# SwitchConnectors.net
KiCad netlist of a schematic drawn in Altium Designer
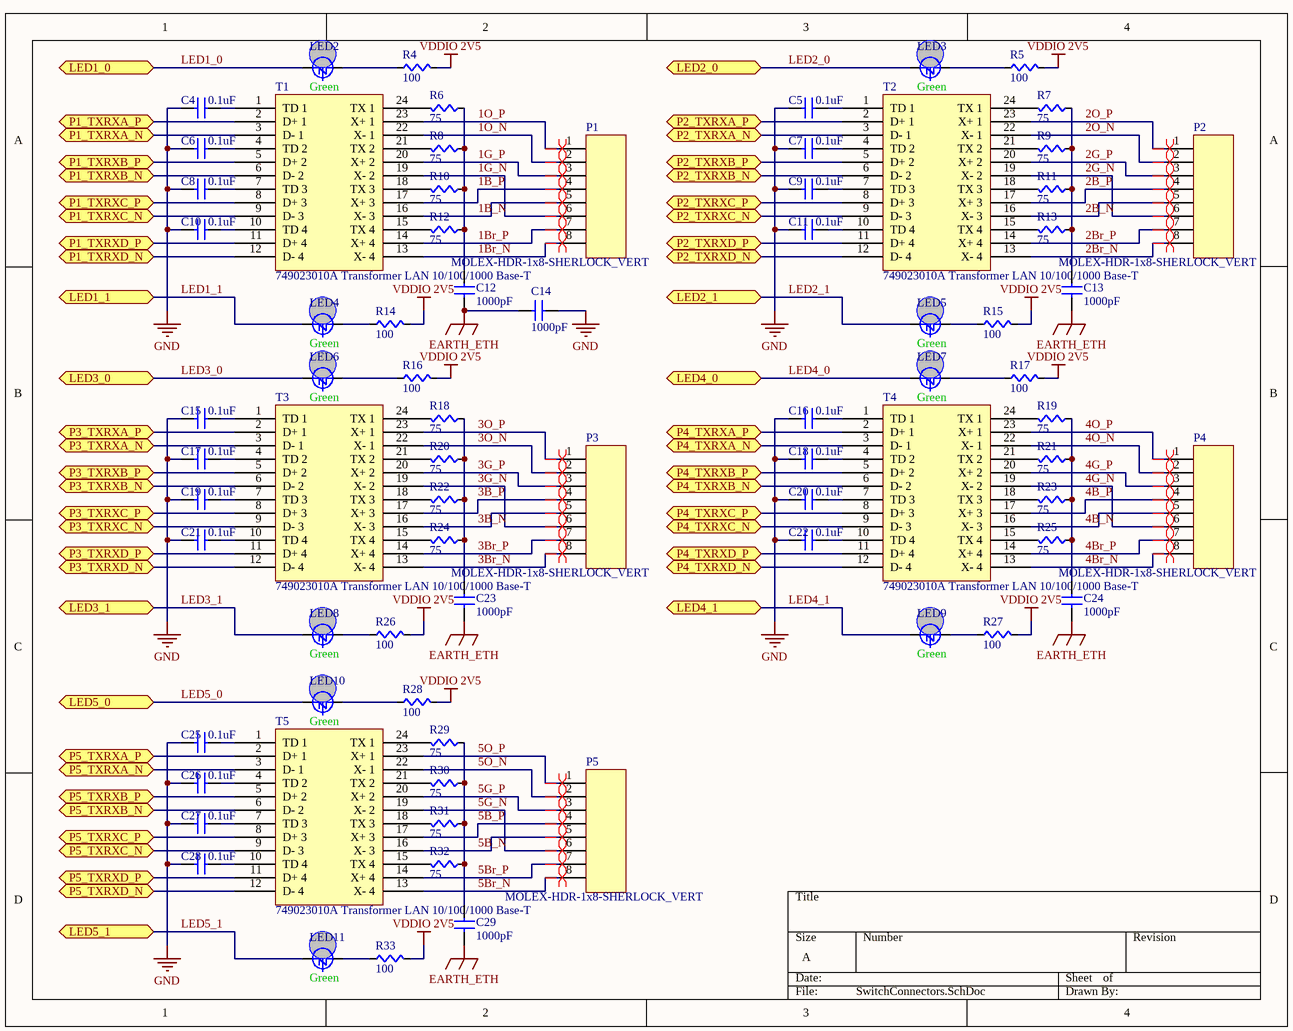
[diagram p0: SwitchConnectors.SchDoc]

(export (version "E")
  (design (tool "Eeschema 10.0.6"))
  (components
    (comp (ref "C4")
      (value "0.1uF")
      (footprint "CAPC0603")
      (fields (field (name "Comment") "Cap"))
      (libsource (lib "Passives") (part "Cap"))
    )
    (comp (ref "C5")
      (value "0.1uF")
      (footprint "CAPC0603")
      (fields (field (name "Comment") "Cap"))
      (libsource (lib "Passives") (part "Cap"))
    )
    (comp (ref "C6")
      (value "0.1uF")
      (footprint "CAPC0603")
      (fields (field (name "Comment") "Cap"))
      (libsource (lib "Passives") (part "Cap"))
    )
    (comp (ref "C7")
      (value "0.1uF")
      (footprint "CAPC0603")
      (fields (field (name "Comment") "Cap"))
      (libsource (lib "Passives") (part "Cap"))
    )
    (comp (ref "C8")
      (value "0.1uF")
      (footprint "CAPC0603")
      (fields (field (name "Comment") "Cap"))
      (libsource (lib "Passives") (part "Cap"))
    )
    (comp (ref "C9")
      (value "0.1uF")
      (footprint "CAPC0603")
      (fields (field (name "Comment") "Cap"))
      (libsource (lib "Passives") (part "Cap"))
    )
    (comp (ref "C10")
      (value "0.1uF")
      (footprint "CAPC0603")
      (fields (field (name "Comment") "Cap"))
      (libsource (lib "Passives") (part "Cap"))
    )
    (comp (ref "C11")
      (value "0.1uF")
      (footprint "CAPC0603")
      (fields (field (name "Comment") "Cap"))
      (libsource (lib "Passives") (part "Cap"))
    )
    (comp (ref "C12")
      (value "1000pF")
      (footprint "CAPC0603")
      (fields (field (name "Comment") "Cap"))
      (libsource (lib "Passives") (part "Cap"))
    )
    (comp (ref "C13")
      (value "1000pF")
      (footprint "CAPC0603")
      (fields (field (name "Comment") "Cap"))
      (libsource (lib "Passives") (part "Cap"))
    )
    (comp (ref "C14")
      (value "1000pF")
      (footprint "CAPC0603")
      (fields (field (name "Comment") "Cap"))
      (libsource (lib "Passives") (part "Cap"))
    )
    (comp (ref "C15")
      (value "0.1uF")
      (footprint "CAPC0603")
      (fields (field (name "Comment") "Cap"))
      (libsource (lib "Passives") (part "Cap"))
    )
    (comp (ref "C16")
      (value "0.1uF")
      (footprint "CAPC0603")
      (fields (field (name "Comment") "Cap"))
      (libsource (lib "Passives") (part "Cap"))
    )
    (comp (ref "C17")
      (value "0.1uF")
      (footprint "CAPC0603")
      (fields (field (name "Comment") "Cap"))
      (libsource (lib "Passives") (part "Cap"))
    )
    (comp (ref "C18")
      (value "0.1uF")
      (footprint "CAPC0603")
      (fields (field (name "Comment") "Cap"))
      (libsource (lib "Passives") (part "Cap"))
    )
    (comp (ref "C19")
      (value "0.1uF")
      (footprint "CAPC0603")
      (fields (field (name "Comment") "Cap"))
      (libsource (lib "Passives") (part "Cap"))
    )
    (comp (ref "C20")
      (value "0.1uF")
      (footprint "CAPC0603")
      (fields (field (name "Comment") "Cap"))
      (libsource (lib "Passives") (part "Cap"))
    )
    (comp (ref "C21")
      (value "0.1uF")
      (footprint "CAPC0603")
      (fields (field (name "Comment") "Cap"))
      (libsource (lib "Passives") (part "Cap"))
    )
    (comp (ref "C22")
      (value "0.1uF")
      (footprint "CAPC0603")
      (fields (field (name "Comment") "Cap"))
      (libsource (lib "Passives") (part "Cap"))
    )
    (comp (ref "C23")
      (value "1000pF")
      (footprint "CAPC0603")
      (fields (field (name "Comment") "Cap"))
      (libsource (lib "Passives") (part "Cap"))
    )
    (comp (ref "C24")
      (value "1000pF")
      (footprint "CAPC0603")
      (fields (field (name "Comment") "Cap"))
      (libsource (lib "Passives") (part "Cap"))
    )
    (comp (ref "C25")
      (value "0.1uF")
      (footprint "CAPC0603")
      (fields (field (name "Comment") "Cap"))
      (libsource (lib "Passives") (part "Cap"))
    )
    (comp (ref "C26")
      (value "0.1uF")
      (footprint "CAPC0603")
      (fields (field (name "Comment") "Cap"))
      (libsource (lib "Passives") (part "Cap"))
    )
    (comp (ref "C27")
      (value "0.1uF")
      (footprint "CAPC0603")
      (fields (field (name "Comment") "Cap"))
      (libsource (lib "Passives") (part "Cap"))
    )
    (comp (ref "C28")
      (value "0.1uF")
      (footprint "CAPC0603")
      (fields (field (name "Comment") "Cap"))
      (libsource (lib "Passives") (part "Cap"))
    )
    (comp (ref "C29")
      (value "1000pF")
      (footprint "CAPC0603")
      (fields (field (name "Comment") "Cap"))
      (libsource (lib "Passives") (part "Cap"))
    )
    (comp (ref "LED2")
      (value "LED")
      (footprint "LED0603")
      (fields (field (name "COLOR") "Green"))
      (libsource (lib "Semiconductors") (part "LED"))
    )
    (comp (ref "LED3")
      (value "LED")
      (footprint "LED0603")
      (fields (field (name "COLOR") "Green"))
      (libsource (lib "Semiconductors") (part "LED"))
    )
    (comp (ref "LED4")
      (value "LED")
      (footprint "LED0603")
      (fields (field (name "COLOR") "Green"))
      (libsource (lib "Semiconductors") (part "LED"))
    )
    (comp (ref "LED5")
      (value "LED")
      (footprint "LED0603")
      (fields (field (name "COLOR") "Green"))
      (libsource (lib "Semiconductors") (part "LED"))
    )
    (comp (ref "LED6")
      (value "LED")
      (footprint "LED0603")
      (fields (field (name "COLOR") "Green"))
      (libsource (lib "Semiconductors") (part "LED"))
    )
    (comp (ref "LED7")
      (value "LED")
      (footprint "LED0603")
      (fields (field (name "COLOR") "Green"))
      (libsource (lib "Semiconductors") (part "LED"))
    )
    (comp (ref "LED8")
      (value "LED")
      (footprint "LED0603")
      (fields (field (name "COLOR") "Green"))
      (libsource (lib "Semiconductors") (part "LED"))
    )
    (comp (ref "LED9")
      (value "LED")
      (footprint "LED0603")
      (fields (field (name "COLOR") "Green"))
      (libsource (lib "Semiconductors") (part "LED"))
    )
    (comp (ref "LED10")
      (value "LED")
      (footprint "LED0603")
      (fields (field (name "COLOR") "Green"))
      (libsource (lib "Semiconductors") (part "LED"))
    )
    (comp (ref "LED11")
      (value "LED")
      (footprint "LED0603")
      (fields (field (name "COLOR") "Green"))
      (libsource (lib "Semiconductors") (part "LED"))
    )
    (comp (ref "P1")
      (value "MOLEX-HDR-1x8-SHERLOCK_VERT")
      (footprint "Connectors:MOLEX-HDR-1X8-SHERLOCK-VERT")
      (description "CONN HEADER 8POS 2MM VERT TIN")
      (libsource (lib "Connectors") (part "MOLEX-HDR-1x8-SHERLOCK_VERT"))
    )
    (comp (ref "P2")
      (value "MOLEX-HDR-1x8-SHERLOCK_VERT")
      (footprint "Connectors:MOLEX-HDR-1X8-SHERLOCK-VERT")
      (description "CONN HEADER 8POS 2MM VERT TIN")
      (libsource (lib "Connectors") (part "MOLEX-HDR-1x8-SHERLOCK_VERT"))
    )
    (comp (ref "P3")
      (value "MOLEX-HDR-1x8-SHERLOCK_VERT")
      (footprint "Connectors:MOLEX-HDR-1X8-SHERLOCK-VERT")
      (description "CONN HEADER 8POS 2MM VERT TIN")
      (libsource (lib "Connectors") (part "MOLEX-HDR-1x8-SHERLOCK_VERT"))
    )
    (comp (ref "P4")
      (value "MOLEX-HDR-1x8-SHERLOCK_VERT")
      (footprint "Connectors:MOLEX-HDR-1X8-SHERLOCK-VERT")
      (description "CONN HEADER 8POS 2MM VERT TIN")
      (libsource (lib "Connectors") (part "MOLEX-HDR-1x8-SHERLOCK_VERT"))
    )
    (comp (ref "P5")
      (value "MOLEX-HDR-1x8-SHERLOCK_VERT")
      (footprint "Connectors:MOLEX-HDR-1X8-SHERLOCK-VERT")
      (description "CONN HEADER 8POS 2MM VERT TIN")
      (libsource (lib "Connectors") (part "MOLEX-HDR-1x8-SHERLOCK_VERT"))
    )
    (comp (ref "R4")
      (value "100")
      (footprint "RES0603")
      (fields (field (name "Comment") "Res"))
      (libsource (lib "Passives") (part "Res"))
    )
    (comp (ref "R5")
      (value "100")
      (footprint "RES0603")
      (fields (field (name "Comment") "Res"))
      (libsource (lib "Passives") (part "Res"))
    )
    (comp (ref "R6")
      (value "75")
      (footprint "RES0603")
      (fields (field (name "Comment") "Res"))
      (libsource (lib "Passives") (part "Res"))
    )
    (comp (ref "R7")
      (value "75")
      (footprint "RES0603")
      (fields (field (name "Comment") "Res"))
      (libsource (lib "Passives") (part "Res"))
    )
    (comp (ref "R8")
      (value "75")
      (footprint "RES0603")
      (fields (field (name "Comment") "Res"))
      (libsource (lib "Passives") (part "Res"))
    )
    (comp (ref "R9")
      (value "75")
      (footprint "RES0603")
      (fields (field (name "Comment") "Res"))
      (libsource (lib "Passives") (part "Res"))
    )
    (comp (ref "R10")
      (value "75")
      (footprint "RES0603")
      (fields (field (name "Comment") "Res"))
      (libsource (lib "Passives") (part "Res"))
    )
    (comp (ref "R11")
      (value "75")
      (footprint "RES0603")
      (fields (field (name "Comment") "Res"))
      (libsource (lib "Passives") (part "Res"))
    )
    (comp (ref "R12")
      (value "75")
      (footprint "RES0603")
      (fields (field (name "Comment") "Res"))
      (libsource (lib "Passives") (part "Res"))
    )
    (comp (ref "R13")
      (value "75")
      (footprint "RES0603")
      (fields (field (name "Comment") "Res"))
      (libsource (lib "Passives") (part "Res"))
    )
    (comp (ref "R14")
      (value "100")
      (footprint "RES0603")
      (fields (field (name "Comment") "Res"))
      (libsource (lib "Passives") (part "Res"))
    )
    (comp (ref "R15")
      (value "100")
      (footprint "RES0603")
      (fields (field (name "Comment") "Res"))
      (libsource (lib "Passives") (part "Res"))
    )
    (comp (ref "R16")
      (value "100")
      (footprint "RES0603")
      (fields (field (name "Comment") "Res"))
      (libsource (lib "Passives") (part "Res"))
    )
    (comp (ref "R17")
      (value "100")
      (footprint "RES0603")
      (fields (field (name "Comment") "Res"))
      (libsource (lib "Passives") (part "Res"))
    )
    (comp (ref "R18")
      (value "75")
      (footprint "RES0603")
      (fields (field (name "Comment") "Res"))
      (libsource (lib "Passives") (part "Res"))
    )
    (comp (ref "R19")
      (value "75")
      (footprint "RES0603")
      (fields (field (name "Comment") "Res"))
      (libsource (lib "Passives") (part "Res"))
    )
    (comp (ref "R20")
      (value "75")
      (footprint "RES0603")
      (fields (field (name "Comment") "Res"))
      (libsource (lib "Passives") (part "Res"))
    )
    (comp (ref "R21")
      (value "75")
      (footprint "RES0603")
      (fields (field (name "Comment") "Res"))
      (libsource (lib "Passives") (part "Res"))
    )
    (comp (ref "R22")
      (value "75")
      (footprint "RES0603")
      (fields (field (name "Comment") "Res"))
      (libsource (lib "Passives") (part "Res"))
    )
    (comp (ref "R23")
      (value "75")
      (footprint "RES0603")
      (fields (field (name "Comment") "Res"))
      (libsource (lib "Passives") (part "Res"))
    )
    (comp (ref "R24")
      (value "75")
      (footprint "RES0603")
      (fields (field (name "Comment") "Res"))
      (libsource (lib "Passives") (part "Res"))
    )
    (comp (ref "R25")
      (value "75")
      (footprint "RES0603")
      (fields (field (name "Comment") "Res"))
      (libsource (lib "Passives") (part "Res"))
    )
    (comp (ref "R26")
      (value "100")
      (footprint "RES0603")
      (fields (field (name "Comment") "Res"))
      (libsource (lib "Passives") (part "Res"))
    )
    (comp (ref "R27")
      (value "100")
      (footprint "RES0603")
      (fields (field (name "Comment") "Res"))
      (libsource (lib "Passives") (part "Res"))
    )
    (comp (ref "R28")
      (value "100")
      (footprint "RES0603")
      (fields (field (name "Comment") "Res"))
      (libsource (lib "Passives") (part "Res"))
    )
    (comp (ref "R29")
      (value "75")
      (footprint "RES0603")
      (fields (field (name "Comment") "Res"))
      (libsource (lib "Passives") (part "Res"))
    )
    (comp (ref "R30")
      (value "75")
      (footprint "RES0603")
      (fields (field (name "Comment") "Res"))
      (libsource (lib "Passives") (part "Res"))
    )
    (comp (ref "R31")
      (value "75")
      (footprint "RES0603")
      (fields (field (name "Comment") "Res"))
      (libsource (lib "Passives") (part "Res"))
    )
    (comp (ref "R32")
      (value "75")
      (footprint "RES0603")
      (fields (field (name "Comment") "Res"))
      (libsource (lib "Passives") (part "Res"))
    )
    (comp (ref "R33")
      (value "100")
      (footprint "RES0603")
      (fields (field (name "Comment") "Res"))
      (libsource (lib "Passives") (part "Res"))
    )
    (comp (ref "T1")
      (value "749023010A Transformer LAN 10/100/1000 Base-T")
      (footprint "ICs:749023010A")
      (description "TRANSFORMER LAN 10/100/1000 SMD")
      (libsource (lib "ICs") (part "749023010A Transformer LAN 10/100/1000 Base-T"))
    )
    (comp (ref "T2")
      (value "749023010A Transformer LAN 10/100/1000 Base-T")
      (footprint "ICs:749023010A")
      (description "TRANSFORMER LAN 10/100/1000 SMD")
      (libsource (lib "ICs") (part "749023010A Transformer LAN 10/100/1000 Base-T"))
    )
    (comp (ref "T3")
      (value "749023010A Transformer LAN 10/100/1000 Base-T")
      (footprint "ICs:749023010A")
      (description "TRANSFORMER LAN 10/100/1000 SMD")
      (libsource (lib "ICs") (part "749023010A Transformer LAN 10/100/1000 Base-T"))
    )
    (comp (ref "T4")
      (value "749023010A Transformer LAN 10/100/1000 Base-T")
      (footprint "ICs:749023010A")
      (description "TRANSFORMER LAN 10/100/1000 SMD")
      (libsource (lib "ICs") (part "749023010A Transformer LAN 10/100/1000 Base-T"))
    )
    (comp (ref "T5")
      (value "749023010A Transformer LAN 10/100/1000 Base-T")
      (footprint "ICs:749023010A")
      (description "TRANSFORMER LAN 10/100/1000 SMD")
      (libsource (lib "ICs") (part "749023010A Transformer LAN 10/100/1000 Base-T"))
    )
  )
  (nets
    (net (code "1") (name "/1B_N") (class "Default")
      (node (ref "P1") (pin "5") (pinfunction "5_5") (pintype "passive"))
      (node (ref "T1") (pin "16") (pinfunction "X-_3_16") (pintype "passive"))
    )
    (net (code "2") (name "/1B_P") (class "Default")
      (node (ref "P1") (pin "4") (pinfunction "4_4") (pintype "passive"))
      (node (ref "T1") (pin "17") (pinfunction "X+_3_17") (pintype "passive"))
    )
    (net (code "3") (name "/1Br_N") (class "Default")
      (node (ref "P1") (pin "8") (pinfunction "8_8") (pintype "passive"))
      (node (ref "T1") (pin "13") (pinfunction "X-_4_13") (pintype "passive"))
    )
    (net (code "4") (name "/1Br_P") (class "Default")
      (node (ref "P1") (pin "7") (pinfunction "7_7") (pintype "passive"))
      (node (ref "T1") (pin "14") (pinfunction "X+_4_14") (pintype "passive"))
    )
    (net (code "5") (name "/1G_N") (class "Default")
      (node (ref "P1") (pin "6") (pinfunction "6_6") (pintype "passive"))
      (node (ref "T1") (pin "19") (pinfunction "X-_2_19") (pintype "passive"))
    )
    (net (code "6") (name "/1G_P") (class "Default")
      (node (ref "P1") (pin "3") (pinfunction "3_3") (pintype "passive"))
      (node (ref "T1") (pin "20") (pinfunction "X+_2_20") (pintype "passive"))
    )
    (net (code "7") (name "/1O_N") (class "Default")
      (node (ref "P1") (pin "2") (pinfunction "2_2") (pintype "passive"))
      (node (ref "T1") (pin "22") (pinfunction "X-_1_22") (pintype "passive"))
    )
    (net (code "8") (name "/1O_P") (class "Default")
      (node (ref "P1") (pin "1") (pinfunction "1_1") (pintype "passive"))
      (node (ref "T1") (pin "23") (pinfunction "X+_1_23") (pintype "passive"))
    )
    (net (code "9") (name "/2B_N") (class "Default")
      (node (ref "P2") (pin "5") (pinfunction "5_5") (pintype "passive"))
      (node (ref "T2") (pin "16") (pinfunction "X-_3_16") (pintype "passive"))
    )
    (net (code "10") (name "/2B_P") (class "Default")
      (node (ref "P2") (pin "4") (pinfunction "4_4") (pintype "passive"))
      (node (ref "T2") (pin "17") (pinfunction "X+_3_17") (pintype "passive"))
    )
    (net (code "11") (name "/2Br_N") (class "Default")
      (node (ref "P2") (pin "8") (pinfunction "8_8") (pintype "passive"))
      (node (ref "T2") (pin "13") (pinfunction "X-_4_13") (pintype "passive"))
    )
    (net (code "12") (name "/2Br_P") (class "Default")
      (node (ref "P2") (pin "7") (pinfunction "7_7") (pintype "passive"))
      (node (ref "T2") (pin "14") (pinfunction "X+_4_14") (pintype "passive"))
    )
    (net (code "13") (name "/2G_N") (class "Default")
      (node (ref "P2") (pin "6") (pinfunction "6_6") (pintype "passive"))
      (node (ref "T2") (pin "19") (pinfunction "X-_2_19") (pintype "passive"))
    )
    (net (code "14") (name "/2G_P") (class "Default")
      (node (ref "P2") (pin "3") (pinfunction "3_3") (pintype "passive"))
      (node (ref "T2") (pin "20") (pinfunction "X+_2_20") (pintype "passive"))
    )
    (net (code "15") (name "/2O_N") (class "Default")
      (node (ref "P2") (pin "2") (pinfunction "2_2") (pintype "passive"))
      (node (ref "T2") (pin "22") (pinfunction "X-_1_22") (pintype "passive"))
    )
    (net (code "16") (name "/2O_P") (class "Default")
      (node (ref "P2") (pin "1") (pinfunction "1_1") (pintype "passive"))
      (node (ref "T2") (pin "23") (pinfunction "X+_1_23") (pintype "passive"))
    )
    (net (code "17") (name "/3B_N") (class "Default")
      (node (ref "P3") (pin "5") (pinfunction "5_5") (pintype "passive"))
      (node (ref "T3") (pin "16") (pinfunction "X-_3_16") (pintype "passive"))
    )
    (net (code "18") (name "/3B_P") (class "Default")
      (node (ref "P3") (pin "4") (pinfunction "4_4") (pintype "passive"))
      (node (ref "T3") (pin "17") (pinfunction "X+_3_17") (pintype "passive"))
    )
    (net (code "19") (name "/3Br_N") (class "Default")
      (node (ref "P3") (pin "8") (pinfunction "8_8") (pintype "passive"))
      (node (ref "T3") (pin "13") (pinfunction "X-_4_13") (pintype "passive"))
    )
    (net (code "20") (name "/3Br_P") (class "Default")
      (node (ref "P3") (pin "7") (pinfunction "7_7") (pintype "passive"))
      (node (ref "T3") (pin "14") (pinfunction "X+_4_14") (pintype "passive"))
    )
    (net (code "21") (name "/3G_N") (class "Default")
      (node (ref "P3") (pin "6") (pinfunction "6_6") (pintype "passive"))
      (node (ref "T3") (pin "19") (pinfunction "X-_2_19") (pintype "passive"))
    )
    (net (code "22") (name "/3G_P") (class "Default")
      (node (ref "P3") (pin "3") (pinfunction "3_3") (pintype "passive"))
      (node (ref "T3") (pin "20") (pinfunction "X+_2_20") (pintype "passive"))
    )
    (net (code "23") (name "/3O_N") (class "Default")
      (node (ref "P3") (pin "2") (pinfunction "2_2") (pintype "passive"))
      (node (ref "T3") (pin "22") (pinfunction "X-_1_22") (pintype "passive"))
    )
    (net (code "24") (name "/3O_P") (class "Default")
      (node (ref "P3") (pin "1") (pinfunction "1_1") (pintype "passive"))
      (node (ref "T3") (pin "23") (pinfunction "X+_1_23") (pintype "passive"))
    )
    (net (code "25") (name "/4B_N") (class "Default")
      (node (ref "P4") (pin "5") (pinfunction "5_5") (pintype "passive"))
      (node (ref "T4") (pin "16") (pinfunction "X-_3_16") (pintype "passive"))
    )
    (net (code "26") (name "/4B_P") (class "Default")
      (node (ref "P4") (pin "4") (pinfunction "4_4") (pintype "passive"))
      (node (ref "T4") (pin "17") (pinfunction "X+_3_17") (pintype "passive"))
    )
    (net (code "27") (name "/4Br_N") (class "Default")
      (node (ref "P4") (pin "8") (pinfunction "8_8") (pintype "passive"))
      (node (ref "T4") (pin "13") (pinfunction "X-_4_13") (pintype "passive"))
    )
    (net (code "28") (name "/4Br_P") (class "Default")
      (node (ref "P4") (pin "7") (pinfunction "7_7") (pintype "passive"))
      (node (ref "T4") (pin "14") (pinfunction "X+_4_14") (pintype "passive"))
    )
    (net (code "29") (name "/4G_N") (class "Default")
      (node (ref "P4") (pin "6") (pinfunction "6_6") (pintype "passive"))
      (node (ref "T4") (pin "19") (pinfunction "X-_2_19") (pintype "passive"))
    )
    (net (code "30") (name "/4G_P") (class "Default")
      (node (ref "P4") (pin "3") (pinfunction "3_3") (pintype "passive"))
      (node (ref "T4") (pin "20") (pinfunction "X+_2_20") (pintype "passive"))
    )
    (net (code "31") (name "/4O_N") (class "Default")
      (node (ref "P4") (pin "2") (pinfunction "2_2") (pintype "passive"))
      (node (ref "T4") (pin "22") (pinfunction "X-_1_22") (pintype "passive"))
    )
    (net (code "32") (name "/4O_P") (class "Default")
      (node (ref "P4") (pin "1") (pinfunction "1_1") (pintype "passive"))
      (node (ref "T4") (pin "23") (pinfunction "X+_1_23") (pintype "passive"))
    )
    (net (code "33") (name "/5B_N") (class "Default")
      (node (ref "P5") (pin "5") (pinfunction "5_5") (pintype "passive"))
      (node (ref "T5") (pin "16") (pinfunction "X-_3_16") (pintype "passive"))
    )
    (net (code "34") (name "/5B_P") (class "Default")
      (node (ref "P5") (pin "4") (pinfunction "4_4") (pintype "passive"))
      (node (ref "T5") (pin "17") (pinfunction "X+_3_17") (pintype "passive"))
    )
    (net (code "35") (name "/5Br_N") (class "Default")
      (node (ref "P5") (pin "8") (pinfunction "8_8") (pintype "passive"))
      (node (ref "T5") (pin "13") (pinfunction "X-_4_13") (pintype "passive"))
    )
    (net (code "36") (name "/5Br_P") (class "Default")
      (node (ref "P5") (pin "7") (pinfunction "7_7") (pintype "passive"))
      (node (ref "T5") (pin "14") (pinfunction "X+_4_14") (pintype "passive"))
    )
    (net (code "37") (name "/5G_N") (class "Default")
      (node (ref "P5") (pin "6") (pinfunction "6_6") (pintype "passive"))
      (node (ref "T5") (pin "19") (pinfunction "X-_2_19") (pintype "passive"))
    )
    (net (code "38") (name "/5G_P") (class "Default")
      (node (ref "P5") (pin "3") (pinfunction "3_3") (pintype "passive"))
      (node (ref "T5") (pin "20") (pinfunction "X+_2_20") (pintype "passive"))
    )
    (net (code "39") (name "/5O_N") (class "Default")
      (node (ref "P5") (pin "2") (pinfunction "2_2") (pintype "passive"))
      (node (ref "T5") (pin "22") (pinfunction "X-_1_22") (pintype "passive"))
    )
    (net (code "40") (name "/5O_P") (class "Default")
      (node (ref "P5") (pin "1") (pinfunction "1_1") (pintype "passive"))
      (node (ref "T5") (pin "23") (pinfunction "X+_1_23") (pintype "passive"))
    )
    (net (code "41") (name "/LED1_0") (class "Default")
      (node (ref "LED2") (pin "C") (pinfunction "C_C") (pintype "passive"))
    )
    (net (code "42") (name "/LED1_1") (class "Default")
      (node (ref "LED4") (pin "C") (pinfunction "C_C") (pintype "passive"))
    )
    (net (code "43") (name "/LED2_0") (class "Default")
      (node (ref "LED3") (pin "C") (pinfunction "C_C") (pintype "passive"))
    )
    (net (code "44") (name "/LED2_1") (class "Default")
      (node (ref "LED5") (pin "C") (pinfunction "C_C") (pintype "passive"))
    )
    (net (code "45") (name "/LED3_0") (class "Default")
      (node (ref "LED6") (pin "C") (pinfunction "C_C") (pintype "passive"))
    )
    (net (code "46") (name "/LED3_1") (class "Default")
      (node (ref "LED8") (pin "C") (pinfunction "C_C") (pintype "passive"))
    )
    (net (code "47") (name "/LED4_0") (class "Default")
      (node (ref "LED7") (pin "C") (pinfunction "C_C") (pintype "passive"))
    )
    (net (code "48") (name "/LED4_1") (class "Default")
      (node (ref "LED9") (pin "C") (pinfunction "C_C") (pintype "passive"))
    )
    (net (code "49") (name "/LED5_0") (class "Default")
      (node (ref "LED10") (pin "C") (pinfunction "C_C") (pintype "passive"))
    )
    (net (code "50") (name "/LED5_1") (class "Default")
      (node (ref "LED11") (pin "C") (pinfunction "C_C") (pintype "passive"))
    )
    (net (code "51") (name "/P1_TXRXA_N") (class "Default")
      (node (ref "T1") (pin "3") (pinfunction "D-_1_3") (pintype "passive"))
    )
    (net (code "52") (name "/P1_TXRXA_P") (class "Default")
      (node (ref "T1") (pin "2") (pinfunction "D+_1_2") (pintype "passive"))
    )
    (net (code "53") (name "/P1_TXRXB_N") (class "Default")
      (node (ref "T1") (pin "6") (pinfunction "D-_2_6") (pintype "passive"))
    )
    (net (code "54") (name "/P1_TXRXB_P") (class "Default")
      (node (ref "T1") (pin "5") (pinfunction "D+_2_5") (pintype "passive"))
    )
    (net (code "55") (name "/P1_TXRXC_N") (class "Default")
      (node (ref "T1") (pin "9") (pinfunction "D-_3_9") (pintype "passive"))
    )
    (net (code "56") (name "/P1_TXRXC_P") (class "Default")
      (node (ref "T1") (pin "8") (pinfunction "D+_3_8") (pintype "passive"))
    )
    (net (code "57") (name "/P1_TXRXD_N") (class "Default")
      (node (ref "T1") (pin "12") (pinfunction "D-_4_12") (pintype "passive"))
    )
    (net (code "58") (name "/P1_TXRXD_P") (class "Default")
      (node (ref "T1") (pin "11") (pinfunction "D+_4_11") (pintype "passive"))
    )
    (net (code "59") (name "/P2_TXRXA_N") (class "Default")
      (node (ref "T2") (pin "3") (pinfunction "D-_1_3") (pintype "passive"))
    )
    (net (code "60") (name "/P2_TXRXA_P") (class "Default")
      (node (ref "T2") (pin "2") (pinfunction "D+_1_2") (pintype "passive"))
    )
    (net (code "61") (name "/P2_TXRXB_N") (class "Default")
      (node (ref "T2") (pin "6") (pinfunction "D-_2_6") (pintype "passive"))
    )
    (net (code "62") (name "/P2_TXRXB_P") (class "Default")
      (node (ref "T2") (pin "5") (pinfunction "D+_2_5") (pintype "passive"))
    )
    (net (code "63") (name "/P2_TXRXC_N") (class "Default")
      (node (ref "T2") (pin "9") (pinfunction "D-_3_9") (pintype "passive"))
    )
    (net (code "64") (name "/P2_TXRXC_P") (class "Default")
      (node (ref "T2") (pin "8") (pinfunction "D+_3_8") (pintype "passive"))
    )
    (net (code "65") (name "/P2_TXRXD_N") (class "Default")
      (node (ref "T2") (pin "12") (pinfunction "D-_4_12") (pintype "passive"))
    )
    (net (code "66") (name "/P2_TXRXD_P") (class "Default")
      (node (ref "T2") (pin "11") (pinfunction "D+_4_11") (pintype "passive"))
    )
    (net (code "67") (name "/P3_TXRXA_N") (class "Default")
      (node (ref "T3") (pin "3") (pinfunction "D-_1_3") (pintype "passive"))
    )
    (net (code "68") (name "/P3_TXRXA_P") (class "Default")
      (node (ref "T3") (pin "2") (pinfunction "D+_1_2") (pintype "passive"))
    )
    (net (code "69") (name "/P3_TXRXB_N") (class "Default")
      (node (ref "T3") (pin "6") (pinfunction "D-_2_6") (pintype "passive"))
    )
    (net (code "70") (name "/P3_TXRXB_P") (class "Default")
      (node (ref "T3") (pin "5") (pinfunction "D+_2_5") (pintype "passive"))
    )
    (net (code "71") (name "/P3_TXRXC_N") (class "Default")
      (node (ref "T3") (pin "9") (pinfunction "D-_3_9") (pintype "passive"))
    )
    (net (code "72") (name "/P3_TXRXC_P") (class "Default")
      (node (ref "T3") (pin "8") (pinfunction "D+_3_8") (pintype "passive"))
    )
    (net (code "73") (name "/P3_TXRXD_N") (class "Default")
      (node (ref "T3") (pin "12") (pinfunction "D-_4_12") (pintype "passive"))
    )
    (net (code "74") (name "/P3_TXRXD_P") (class "Default")
      (node (ref "T3") (pin "11") (pinfunction "D+_4_11") (pintype "passive"))
    )
    (net (code "75") (name "/P4_TXRXA_N") (class "Default")
      (node (ref "T4") (pin "3") (pinfunction "D-_1_3") (pintype "passive"))
    )
    (net (code "76") (name "/P4_TXRXA_P") (class "Default")
      (node (ref "T4") (pin "2") (pinfunction "D+_1_2") (pintype "passive"))
    )
    (net (code "77") (name "/P4_TXRXB_N") (class "Default")
      (node (ref "T4") (pin "6") (pinfunction "D-_2_6") (pintype "passive"))
    )
    (net (code "78") (name "/P4_TXRXB_P") (class "Default")
      (node (ref "T4") (pin "5") (pinfunction "D+_2_5") (pintype "passive"))
    )
    (net (code "79") (name "/P4_TXRXC_N") (class "Default")
      (node (ref "T4") (pin "9") (pinfunction "D-_3_9") (pintype "passive"))
    )
    (net (code "80") (name "/P4_TXRXC_P") (class "Default")
      (node (ref "T4") (pin "8") (pinfunction "D+_3_8") (pintype "passive"))
    )
    (net (code "81") (name "/P4_TXRXD_N") (class "Default")
      (node (ref "T4") (pin "12") (pinfunction "D-_4_12") (pintype "passive"))
    )
    (net (code "82") (name "/P4_TXRXD_P") (class "Default")
      (node (ref "T4") (pin "11") (pinfunction "D+_4_11") (pintype "passive"))
    )
    (net (code "83") (name "/P5_TXRXA_N") (class "Default")
      (node (ref "T5") (pin "3") (pinfunction "D-_1_3") (pintype "passive"))
    )
    (net (code "84") (name "/P5_TXRXA_P") (class "Default")
      (node (ref "T5") (pin "2") (pinfunction "D+_1_2") (pintype "passive"))
    )
    (net (code "85") (name "/P5_TXRXB_N") (class "Default")
      (node (ref "T5") (pin "6") (pinfunction "D-_2_6") (pintype "passive"))
    )
    (net (code "86") (name "/P5_TXRXB_P") (class "Default")
      (node (ref "T5") (pin "5") (pinfunction "D+_2_5") (pintype "passive"))
    )
    (net (code "87") (name "/P5_TXRXC_N") (class "Default")
      (node (ref "T5") (pin "9") (pinfunction "D-_3_9") (pintype "passive"))
    )
    (net (code "88") (name "/P5_TXRXC_P") (class "Default")
      (node (ref "T5") (pin "8") (pinfunction "D+_3_8") (pintype "passive"))
    )
    (net (code "89") (name "/P5_TXRXD_N") (class "Default")
      (node (ref "T5") (pin "12") (pinfunction "D-_4_12") (pintype "passive"))
    )
    (net (code "90") (name "/P5_TXRXD_P") (class "Default")
      (node (ref "T5") (pin "11") (pinfunction "D+_4_11") (pintype "passive"))
    )
    (net (code "91") (name "EARTH_ETH") (class "Default")
      (node (ref "C12") (pin "1") (pinfunction "A_1") (pintype "passive"))
      (node (ref "C13") (pin "1") (pinfunction "A_1") (pintype "passive"))
      (node (ref "C14") (pin "2") (pinfunction "B_2") (pintype "passive"))
      (node (ref "C23") (pin "1") (pinfunction "A_1") (pintype "passive"))
      (node (ref "C24") (pin "1") (pinfunction "A_1") (pintype "passive"))
      (node (ref "C29") (pin "1") (pinfunction "A_1") (pintype "passive"))
    )
    (net (code "92") (name "GND") (class "Default")
      (node (ref "C10") (pin "1") (pinfunction "A_1") (pintype "passive"))
      (node (ref "C11") (pin "1") (pinfunction "A_1") (pintype "passive"))
      (node (ref "C14") (pin "1") (pinfunction "A_1") (pintype "passive"))
      (node (ref "C15") (pin "1") (pinfunction "A_1") (pintype "passive"))
      (node (ref "C16") (pin "1") (pinfunction "A_1") (pintype "passive"))
      (node (ref "C17") (pin "1") (pinfunction "A_1") (pintype "passive"))
      (node (ref "C18") (pin "1") (pinfunction "A_1") (pintype "passive"))
      (node (ref "C19") (pin "1") (pinfunction "A_1") (pintype "passive"))
      (node (ref "C20") (pin "1") (pinfunction "A_1") (pintype "passive"))
      (node (ref "C21") (pin "1") (pinfunction "A_1") (pintype "passive"))
      (node (ref "C22") (pin "1") (pinfunction "A_1") (pintype "passive"))
      (node (ref "C25") (pin "1") (pinfunction "A_1") (pintype "passive"))
      (node (ref "C26") (pin "1") (pinfunction "A_1") (pintype "passive"))
      (node (ref "C27") (pin "1") (pinfunction "A_1") (pintype "passive"))
      (node (ref "C28") (pin "1") (pinfunction "A_1") (pintype "passive"))
      (node (ref "C4") (pin "1") (pinfunction "A_1") (pintype "passive"))
      (node (ref "C5") (pin "1") (pinfunction "A_1") (pintype "passive"))
      (node (ref "C6") (pin "1") (pinfunction "A_1") (pintype "passive"))
      (node (ref "C7") (pin "1") (pinfunction "A_1") (pintype "passive"))
      (node (ref "C8") (pin "1") (pinfunction "A_1") (pintype "passive"))
      (node (ref "C9") (pin "1") (pinfunction "A_1") (pintype "passive"))
    )
    (net (code "93") (name "Net-(C4-B)") (class "Default")
      (node (ref "C4") (pin "2") (pinfunction "B_2") (pintype "passive"))
      (node (ref "T1") (pin "1") (pinfunction "TD_1_1") (pintype "passive"))
    )
    (net (code "94") (name "Net-(C5-B)") (class "Default")
      (node (ref "C5") (pin "2") (pinfunction "B_2") (pintype "passive"))
      (node (ref "T2") (pin "1") (pinfunction "TD_1_1") (pintype "passive"))
    )
    (net (code "95") (name "Net-(C6-B)") (class "Default")
      (node (ref "C6") (pin "2") (pinfunction "B_2") (pintype "passive"))
      (node (ref "T1") (pin "4") (pinfunction "TD_2_4") (pintype "passive"))
    )
    (net (code "96") (name "Net-(C7-B)") (class "Default")
      (node (ref "C7") (pin "2") (pinfunction "B_2") (pintype "passive"))
      (node (ref "T2") (pin "4") (pinfunction "TD_2_4") (pintype "passive"))
    )
    (net (code "97") (name "Net-(C8-B)") (class "Default")
      (node (ref "C8") (pin "2") (pinfunction "B_2") (pintype "passive"))
      (node (ref "T1") (pin "7") (pinfunction "TD_3_7") (pintype "passive"))
    )
    (net (code "98") (name "Net-(C9-B)") (class "Default")
      (node (ref "C9") (pin "2") (pinfunction "B_2") (pintype "passive"))
      (node (ref "T2") (pin "7") (pinfunction "TD_3_7") (pintype "passive"))
    )
    (net (code "99") (name "Net-(C10-B)") (class "Default")
      (node (ref "C10") (pin "2") (pinfunction "B_2") (pintype "passive"))
      (node (ref "T1") (pin "10") (pinfunction "TD_4_10") (pintype "passive"))
    )
    (net (code "100") (name "Net-(C11-B)") (class "Default")
      (node (ref "C11") (pin "2") (pinfunction "B_2") (pintype "passive"))
      (node (ref "T2") (pin "10") (pinfunction "TD_4_10") (pintype "passive"))
    )
    (net (code "101") (name "Net-(C12-B)") (class "Default")
      (node (ref "C12") (pin "2") (pinfunction "B_2") (pintype "passive"))
      (node (ref "R10") (pin "2") (pinfunction "B_2") (pintype "passive"))
      (node (ref "R12") (pin "2") (pinfunction "B_2") (pintype "passive"))
      (node (ref "R6") (pin "2") (pinfunction "B_2") (pintype "passive"))
      (node (ref "R8") (pin "2") (pinfunction "B_2") (pintype "passive"))
    )
    (net (code "102") (name "Net-(C13-B)") (class "Default")
      (node (ref "C13") (pin "2") (pinfunction "B_2") (pintype "passive"))
      (node (ref "R11") (pin "2") (pinfunction "B_2") (pintype "passive"))
      (node (ref "R13") (pin "2") (pinfunction "B_2") (pintype "passive"))
      (node (ref "R7") (pin "2") (pinfunction "B_2") (pintype "passive"))
      (node (ref "R9") (pin "2") (pinfunction "B_2") (pintype "passive"))
    )
    (net (code "103") (name "Net-(C15-B)") (class "Default")
      (node (ref "C15") (pin "2") (pinfunction "B_2") (pintype "passive"))
      (node (ref "T3") (pin "1") (pinfunction "TD_1_1") (pintype "passive"))
    )
    (net (code "104") (name "Net-(C16-B)") (class "Default")
      (node (ref "C16") (pin "2") (pinfunction "B_2") (pintype "passive"))
      (node (ref "T4") (pin "1") (pinfunction "TD_1_1") (pintype "passive"))
    )
    (net (code "105") (name "Net-(C17-B)") (class "Default")
      (node (ref "C17") (pin "2") (pinfunction "B_2") (pintype "passive"))
      (node (ref "T3") (pin "4") (pinfunction "TD_2_4") (pintype "passive"))
    )
    (net (code "106") (name "Net-(C18-B)") (class "Default")
      (node (ref "C18") (pin "2") (pinfunction "B_2") (pintype "passive"))
      (node (ref "T4") (pin "4") (pinfunction "TD_2_4") (pintype "passive"))
    )
    (net (code "107") (name "Net-(C19-B)") (class "Default")
      (node (ref "C19") (pin "2") (pinfunction "B_2") (pintype "passive"))
      (node (ref "T3") (pin "7") (pinfunction "TD_3_7") (pintype "passive"))
    )
    (net (code "108") (name "Net-(C20-B)") (class "Default")
      (node (ref "C20") (pin "2") (pinfunction "B_2") (pintype "passive"))
      (node (ref "T4") (pin "7") (pinfunction "TD_3_7") (pintype "passive"))
    )
    (net (code "109") (name "Net-(C21-B)") (class "Default")
      (node (ref "C21") (pin "2") (pinfunction "B_2") (pintype "passive"))
      (node (ref "T3") (pin "10") (pinfunction "TD_4_10") (pintype "passive"))
    )
    (net (code "110") (name "Net-(C22-B)") (class "Default")
      (node (ref "C22") (pin "2") (pinfunction "B_2") (pintype "passive"))
      (node (ref "T4") (pin "10") (pinfunction "TD_4_10") (pintype "passive"))
    )
    (net (code "111") (name "Net-(C23-B)") (class "Default")
      (node (ref "C23") (pin "2") (pinfunction "B_2") (pintype "passive"))
      (node (ref "R18") (pin "2") (pinfunction "B_2") (pintype "passive"))
      (node (ref "R20") (pin "2") (pinfunction "B_2") (pintype "passive"))
      (node (ref "R22") (pin "2") (pinfunction "B_2") (pintype "passive"))
      (node (ref "R24") (pin "2") (pinfunction "B_2") (pintype "passive"))
    )
    (net (code "112") (name "Net-(C24-B)") (class "Default")
      (node (ref "C24") (pin "2") (pinfunction "B_2") (pintype "passive"))
      (node (ref "R19") (pin "2") (pinfunction "B_2") (pintype "passive"))
      (node (ref "R21") (pin "2") (pinfunction "B_2") (pintype "passive"))
      (node (ref "R23") (pin "2") (pinfunction "B_2") (pintype "passive"))
      (node (ref "R25") (pin "2") (pinfunction "B_2") (pintype "passive"))
    )
    (net (code "113") (name "Net-(C25-B)") (class "Default")
      (node (ref "C25") (pin "2") (pinfunction "B_2") (pintype "passive"))
      (node (ref "T5") (pin "1") (pinfunction "TD_1_1") (pintype "passive"))
    )
    (net (code "114") (name "Net-(C26-B)") (class "Default")
      (node (ref "C26") (pin "2") (pinfunction "B_2") (pintype "passive"))
      (node (ref "T5") (pin "4") (pinfunction "TD_2_4") (pintype "passive"))
    )
    (net (code "115") (name "Net-(C27-B)") (class "Default")
      (node (ref "C27") (pin "2") (pinfunction "B_2") (pintype "passive"))
      (node (ref "T5") (pin "7") (pinfunction "TD_3_7") (pintype "passive"))
    )
    (net (code "116") (name "Net-(C28-B)") (class "Default")
      (node (ref "C28") (pin "2") (pinfunction "B_2") (pintype "passive"))
      (node (ref "T5") (pin "10") (pinfunction "TD_4_10") (pintype "passive"))
    )
    (net (code "117") (name "Net-(C29-B)") (class "Default")
      (node (ref "C29") (pin "2") (pinfunction "B_2") (pintype "passive"))
      (node (ref "R29") (pin "2") (pinfunction "B_2") (pintype "passive"))
      (node (ref "R30") (pin "2") (pinfunction "B_2") (pintype "passive"))
      (node (ref "R31") (pin "2") (pinfunction "B_2") (pintype "passive"))
      (node (ref "R32") (pin "2") (pinfunction "B_2") (pintype "passive"))
    )
    (net (code "118") (name "Net-(R4-B)") (class "Default")
      (node (ref "LED2") (pin "A") (pinfunction "A_A") (pintype "passive"))
      (node (ref "R4") (pin "2") (pinfunction "B_2") (pintype "passive"))
    )
    (net (code "119") (name "Net-(R5-B)") (class "Default")
      (node (ref "LED3") (pin "A") (pinfunction "A_A") (pintype "passive"))
      (node (ref "R5") (pin "2") (pinfunction "B_2") (pintype "passive"))
    )
    (net (code "120") (name "Net-(R6-A)") (class "Default")
      (node (ref "R6") (pin "1") (pinfunction "A_1") (pintype "passive"))
      (node (ref "T1") (pin "24") (pinfunction "TX_1_24") (pintype "passive"))
    )
    (net (code "121") (name "Net-(R7-A)") (class "Default")
      (node (ref "R7") (pin "1") (pinfunction "A_1") (pintype "passive"))
      (node (ref "T2") (pin "24") (pinfunction "TX_1_24") (pintype "passive"))
    )
    (net (code "122") (name "Net-(R8-A)") (class "Default")
      (node (ref "R8") (pin "1") (pinfunction "A_1") (pintype "passive"))
      (node (ref "T1") (pin "21") (pinfunction "TX_2_21") (pintype "passive"))
    )
    (net (code "123") (name "Net-(R9-A)") (class "Default")
      (node (ref "R9") (pin "1") (pinfunction "A_1") (pintype "passive"))
      (node (ref "T2") (pin "21") (pinfunction "TX_2_21") (pintype "passive"))
    )
    (net (code "124") (name "Net-(R10-A)") (class "Default")
      (node (ref "R10") (pin "1") (pinfunction "A_1") (pintype "passive"))
      (node (ref "T1") (pin "18") (pinfunction "TX_3_18") (pintype "passive"))
    )
    (net (code "125") (name "Net-(R11-A)") (class "Default")
      (node (ref "R11") (pin "1") (pinfunction "A_1") (pintype "passive"))
      (node (ref "T2") (pin "18") (pinfunction "TX_3_18") (pintype "passive"))
    )
    (net (code "126") (name "Net-(R12-A)") (class "Default")
      (node (ref "R12") (pin "1") (pinfunction "A_1") (pintype "passive"))
      (node (ref "T1") (pin "15") (pinfunction "TX_4_15") (pintype "passive"))
    )
    (net (code "127") (name "Net-(R13-A)") (class "Default")
      (node (ref "R13") (pin "1") (pinfunction "A_1") (pintype "passive"))
      (node (ref "T2") (pin "15") (pinfunction "TX_4_15") (pintype "passive"))
    )
    (net (code "128") (name "Net-(R14-B)") (class "Default")
      (node (ref "LED4") (pin "A") (pinfunction "A_A") (pintype "passive"))
      (node (ref "R14") (pin "2") (pinfunction "B_2") (pintype "passive"))
    )
    (net (code "129") (name "Net-(R15-B)") (class "Default")
      (node (ref "LED5") (pin "A") (pinfunction "A_A") (pintype "passive"))
      (node (ref "R15") (pin "2") (pinfunction "B_2") (pintype "passive"))
    )
    (net (code "130") (name "Net-(R16-B)") (class "Default")
      (node (ref "LED6") (pin "A") (pinfunction "A_A") (pintype "passive"))
      (node (ref "R16") (pin "2") (pinfunction "B_2") (pintype "passive"))
    )
    (net (code "131") (name "Net-(R17-B)") (class "Default")
      (node (ref "LED7") (pin "A") (pinfunction "A_A") (pintype "passive"))
      (node (ref "R17") (pin "2") (pinfunction "B_2") (pintype "passive"))
    )
    (net (code "132") (name "Net-(R18-A)") (class "Default")
      (node (ref "R18") (pin "1") (pinfunction "A_1") (pintype "passive"))
      (node (ref "T3") (pin "24") (pinfunction "TX_1_24") (pintype "passive"))
    )
    (net (code "133") (name "Net-(R19-A)") (class "Default")
      (node (ref "R19") (pin "1") (pinfunction "A_1") (pintype "passive"))
      (node (ref "T4") (pin "24") (pinfunction "TX_1_24") (pintype "passive"))
    )
    (net (code "134") (name "Net-(R20-A)") (class "Default")
      (node (ref "R20") (pin "1") (pinfunction "A_1") (pintype "passive"))
      (node (ref "T3") (pin "21") (pinfunction "TX_2_21") (pintype "passive"))
    )
    (net (code "135") (name "Net-(R21-A)") (class "Default")
      (node (ref "R21") (pin "1") (pinfunction "A_1") (pintype "passive"))
      (node (ref "T4") (pin "21") (pinfunction "TX_2_21") (pintype "passive"))
    )
    (net (code "136") (name "Net-(R22-A)") (class "Default")
      (node (ref "R22") (pin "1") (pinfunction "A_1") (pintype "passive"))
      (node (ref "T3") (pin "18") (pinfunction "TX_3_18") (pintype "passive"))
    )
    (net (code "137") (name "Net-(R23-A)") (class "Default")
      (node (ref "R23") (pin "1") (pinfunction "A_1") (pintype "passive"))
      (node (ref "T4") (pin "18") (pinfunction "TX_3_18") (pintype "passive"))
    )
    (net (code "138") (name "Net-(R24-A)") (class "Default")
      (node (ref "R24") (pin "1") (pinfunction "A_1") (pintype "passive"))
      (node (ref "T3") (pin "15") (pinfunction "TX_4_15") (pintype "passive"))
    )
    (net (code "139") (name "Net-(R25-A)") (class "Default")
      (node (ref "R25") (pin "1") (pinfunction "A_1") (pintype "passive"))
      (node (ref "T4") (pin "15") (pinfunction "TX_4_15") (pintype "passive"))
    )
    (net (code "140") (name "Net-(R26-B)") (class "Default")
      (node (ref "LED8") (pin "A") (pinfunction "A_A") (pintype "passive"))
      (node (ref "R26") (pin "2") (pinfunction "B_2") (pintype "passive"))
    )
    (net (code "141") (name "Net-(R27-B)") (class "Default")
      (node (ref "LED9") (pin "A") (pinfunction "A_A") (pintype "passive"))
      (node (ref "R27") (pin "2") (pinfunction "B_2") (pintype "passive"))
    )
    (net (code "142") (name "Net-(R28-B)") (class "Default")
      (node (ref "LED10") (pin "A") (pinfunction "A_A") (pintype "passive"))
      (node (ref "R28") (pin "2") (pinfunction "B_2") (pintype "passive"))
    )
    (net (code "143") (name "Net-(R29-A)") (class "Default")
      (node (ref "R29") (pin "1") (pinfunction "A_1") (pintype "passive"))
      (node (ref "T5") (pin "24") (pinfunction "TX_1_24") (pintype "passive"))
    )
    (net (code "144") (name "Net-(R30-A)") (class "Default")
      (node (ref "R30") (pin "1") (pinfunction "A_1") (pintype "passive"))
      (node (ref "T5") (pin "21") (pinfunction "TX_2_21") (pintype "passive"))
    )
    (net (code "145") (name "Net-(R31-A)") (class "Default")
      (node (ref "R31") (pin "1") (pinfunction "A_1") (pintype "passive"))
      (node (ref "T5") (pin "18") (pinfunction "TX_3_18") (pintype "passive"))
    )
    (net (code "146") (name "Net-(R32-A)") (class "Default")
      (node (ref "R32") (pin "1") (pinfunction "A_1") (pintype "passive"))
      (node (ref "T5") (pin "15") (pinfunction "TX_4_15") (pintype "passive"))
    )
    (net (code "147") (name "Net-(R33-B)") (class "Default")
      (node (ref "LED11") (pin "A") (pinfunction "A_A") (pintype "passive"))
      (node (ref "R33") (pin "2") (pinfunction "B_2") (pintype "passive"))
    )
    (net (code "148") (name "VDDIO 2V5") (class "Default")
      (node (ref "R14") (pin "1") (pinfunction "A_1") (pintype "passive"))
      (node (ref "R15") (pin "1") (pinfunction "A_1") (pintype "passive"))
      (node (ref "R16") (pin "1") (pinfunction "A_1") (pintype "passive"))
      (node (ref "R17") (pin "1") (pinfunction "A_1") (pintype "passive"))
      (node (ref "R26") (pin "1") (pinfunction "A_1") (pintype "passive"))
      (node (ref "R27") (pin "1") (pinfunction "A_1") (pintype "passive"))
      (node (ref "R28") (pin "1") (pinfunction "A_1") (pintype "passive"))
      (node (ref "R33") (pin "1") (pinfunction "A_1") (pintype "passive"))
      (node (ref "R4") (pin "1") (pinfunction "A_1") (pintype "passive"))
      (node (ref "R5") (pin "1") (pinfunction "A_1") (pintype "passive"))
    )
  )
)
